# USB_PD.net
KiCad netlist of a schematic drawn in Altium Designer
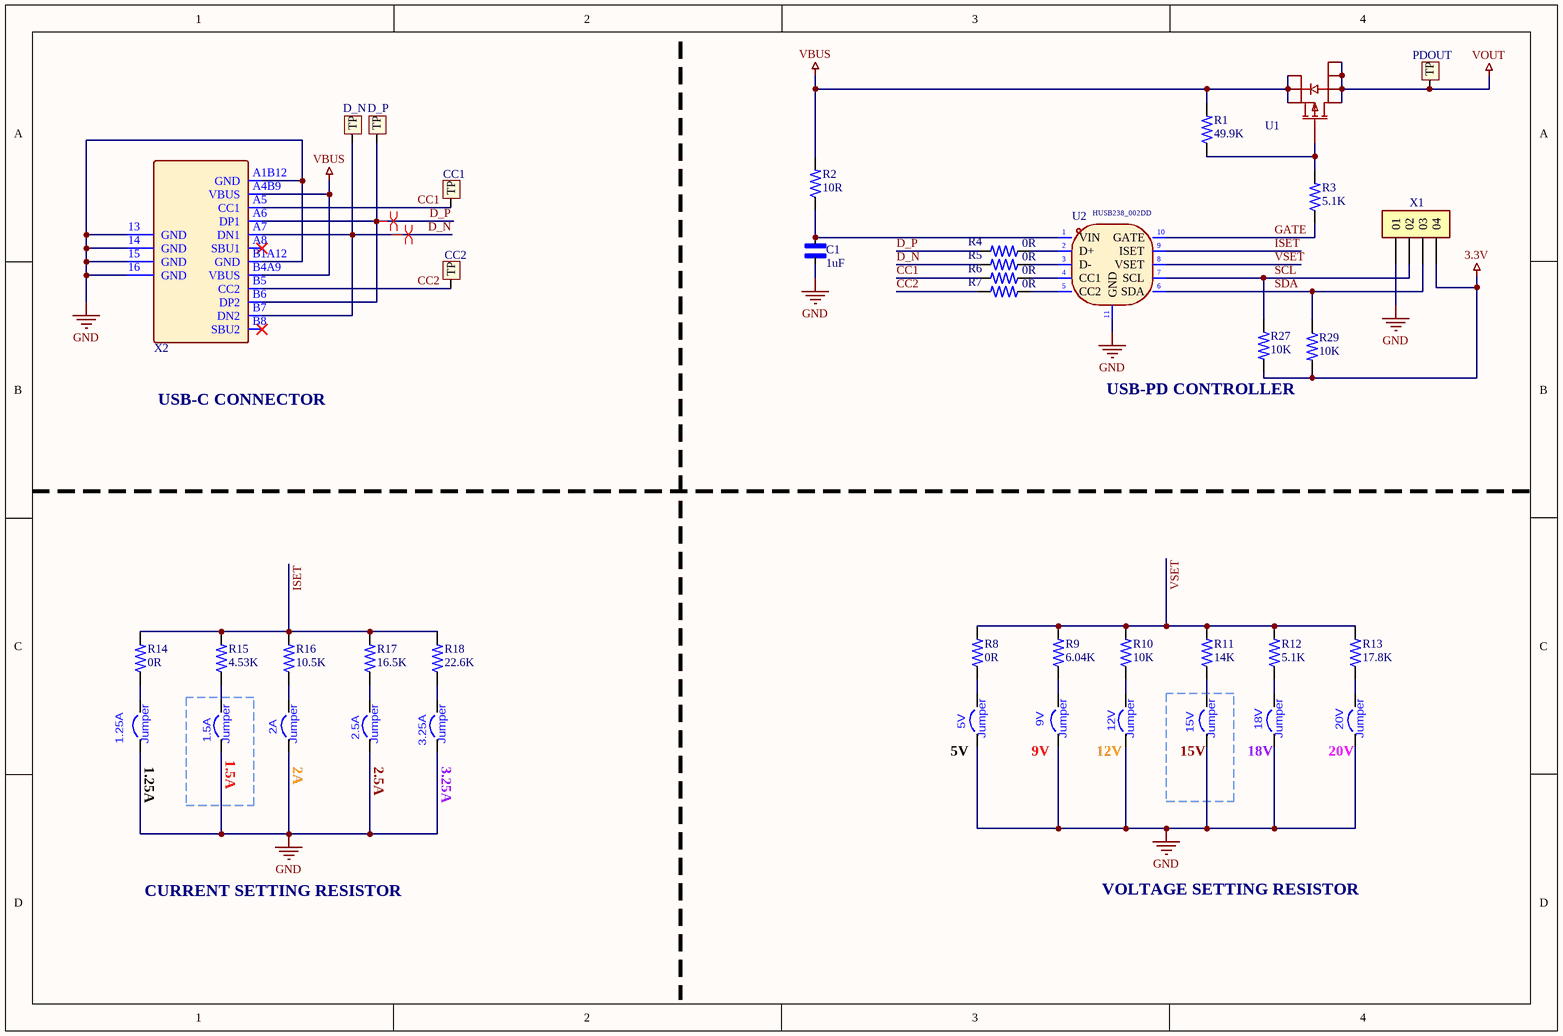
[diagram p0: USB_PD.SchDoc]

(export (version "E")
  (design (tool "Eeschema 10.0.6"))
  (components
    (comp (ref "1.5A")
      (value "Jumper")
      (footprint "PAD-JUMPER-2-NC_BY_PASTE_YES_SILK")
      (description "SMD JUMPER")
      (libsource (lib "USB_PD_DVD") (part "JUMPER SOLDER BRIDGE"))
    )
    (comp (ref "1.25A")
      (value "Jumper")
      (footprint "PAD-JUMPER-2-NC_BY_PASTE_YES_SILK")
      (description "SMD JUMPER")
      (libsource (lib "USB_PD_DVD") (part "JUMPER SOLDER BRIDGE"))
    )
    (comp (ref "2.5A")
      (value "Jumper")
      (footprint "PAD-JUMPER-2-NC_BY_PASTE_YES_SILK")
      (description "SMD JUMPER")
      (libsource (lib "USB_PD_DVD") (part "JUMPER SOLDER BRIDGE"))
    )
    (comp (ref "2A")
      (value "Jumper")
      (footprint "PAD-JUMPER-2-NC_BY_PASTE_YES_SILK")
      (description "SMD JUMPER")
      (libsource (lib "USB_PD_DVD") (part "JUMPER SOLDER BRIDGE"))
    )
    (comp (ref "3.25A")
      (value "Jumper")
      (footprint "PAD-JUMPER-2-NC_BY_PASTE_YES_SILK")
      (description "SMD JUMPER")
      (libsource (lib "USB_PD_DVD") (part "JUMPER SOLDER BRIDGE"))
    )
    (comp (ref "5V")
      (value "Jumper")
      (footprint "PAD-JUMPER-2-NC_BY_PASTE_YES_SILK")
      (description "SMD JUMPER")
      (libsource (lib "USB_PD_DVD") (part "JUMPER SOLDER BRIDGE"))
    )
    (comp (ref "9V")
      (value "Jumper")
      (footprint "PAD-JUMPER-2-NC_BY_PASTE_YES_SILK")
      (description "SMD JUMPER")
      (libsource (lib "USB_PD_DVD") (part "JUMPER SOLDER BRIDGE"))
    )
    (comp (ref "12V")
      (value "Jumper")
      (footprint "PAD-JUMPER-2-NC_BY_PASTE_YES_SILK")
      (description "SMD JUMPER")
      (libsource (lib "USB_PD_DVD") (part "JUMPER SOLDER BRIDGE"))
    )
    (comp (ref "15V")
      (value "Jumper")
      (footprint "PAD-JUMPER-2-NC_BY_PASTE_YES_SILK")
      (description "SMD JUMPER")
      (libsource (lib "USB_PD_DVD") (part "JUMPER SOLDER BRIDGE"))
    )
    (comp (ref "18V")
      (value "Jumper")
      (footprint "PAD-JUMPER-2-NC_BY_PASTE_YES_SILK")
      (description "SMD JUMPER")
      (libsource (lib "USB_PD_DVD") (part "JUMPER SOLDER BRIDGE"))
    )
    (comp (ref "20V")
      (value "Jumper")
      (footprint "PAD-JUMPER-2-NC_BY_PASTE_YES_SILK")
      (description "SMD JUMPER")
      (libsource (lib "USB_PD_DVD") (part "JUMPER SOLDER BRIDGE"))
    )
    (comp (ref "C1")
      (value "1uF")
      (footprint "CAP 0402")
      (fields
        (field (name "VOLTAGE") "50V")
        (field (name "TOLERANCE") "±10%")
        (field (name "Comment") "SMD capacitor")
      )
      (libsource (lib "USB_PD_DVD") (part "CAP_SMD_CERAMIC"))
    )
    (comp (ref "CC1")
      (value "TEST POINT")
      (footprint "TESTPOINT")
      (libsource (lib "USB_PD_DVD") (part "TEST POINT"))
    )
    (comp (ref "CC2")
      (value "TEST POINT")
      (footprint "TESTPOINT")
      (libsource (lib "USB_PD_DVD") (part "TEST POINT"))
    )
    (comp (ref "D_N")
      (value "TEST POINT")
      (footprint "TESTPOINT")
      (libsource (lib "USB_PD_DVD") (part "TEST POINT"))
    )
    (comp (ref "D_P")
      (value "TEST POINT")
      (footprint "TESTPOINT")
      (libsource (lib "USB_PD_DVD") (part "TEST POINT"))
    )
    (comp (ref "PDOUT")
      (value "TEST POINT")
      (footprint "TESTPOINT")
      (libsource (lib "USB_PD_DVD") (part "TEST POINT"))
    )
    (comp (ref "R1")
      (value "49.9K")
      (footprint "RES_1206")
      (fields (field (name "TOLERANCE") "±5%") (field (name "Comment") "SMD resistor"))
      (libsource (lib "USB_PD_DVD") (part "RES_SMD_CERAMIC"))
    )
    (comp (ref "R2")
      (value "10R")
      (footprint "RES_0603")
      (fields (field (name "TOLERANCE") "±5%") (field (name "Comment") "SMD resistor"))
      (libsource (lib "USB_PD_DVD") (part "RES_SMD_CERAMIC"))
    )
    (comp (ref "R3")
      (value "5.1K")
      (footprint "RES_1206")
      (fields (field (name "TOLERANCE") "±5%") (field (name "Comment") "SMD resistor"))
      (libsource (lib "USB_PD_DVD") (part "RES_SMD_CERAMIC"))
    )
    (comp (ref "R4")
      (value "0R")
      (footprint "RES 0402")
      (fields (field (name "TOLERANCE") "±5%") (field (name "Comment") "SMD resistor"))
      (libsource (lib "USB_PD_DVD") (part "RES_SMD_CERAMIC"))
    )
    (comp (ref "R5")
      (value "0R")
      (footprint "RES 0402")
      (fields (field (name "TOLERANCE") "±5%") (field (name "Comment") "SMD resistor"))
      (libsource (lib "USB_PD_DVD") (part "RES_SMD_CERAMIC"))
    )
    (comp (ref "R6")
      (value "0R")
      (footprint "RES 0402")
      (fields (field (name "TOLERANCE") "±5%") (field (name "Comment") "SMD resistor"))
      (libsource (lib "USB_PD_DVD") (part "RES_SMD_CERAMIC"))
    )
    (comp (ref "R7")
      (value "0R")
      (footprint "RES 0402")
      (fields (field (name "TOLERANCE") "±5%") (field (name "Comment") "SMD resistor"))
      (libsource (lib "USB_PD_DVD") (part "RES_SMD_CERAMIC"))
    )
    (comp (ref "R8")
      (value "0R")
      (footprint "RES 0402")
      (fields (field (name "TOLERANCE") "±5%") (field (name "Comment") "SMD resistor"))
      (libsource (lib "USB_PD_DVD") (part "RES_SMD_CERAMIC"))
    )
    (comp (ref "R9")
      (value "6.04K")
      (footprint "RES 0402")
      (fields (field (name "TOLERANCE") "±5%") (field (name "Comment") "SMD resistor"))
      (libsource (lib "USB_PD_DVD") (part "RES_SMD_CERAMIC"))
    )
    (comp (ref "R10")
      (value "10K")
      (footprint "RES 0402")
      (fields (field (name "TOLERANCE") "±5%") (field (name "Comment") "SMD resistor"))
      (libsource (lib "USB_PD_DVD") (part "RES_SMD_CERAMIC"))
    )
    (comp (ref "R11")
      (value "14K")
      (footprint "RES 0402")
      (fields (field (name "TOLERANCE") "±5%") (field (name "Comment") "SMD resistor"))
      (libsource (lib "USB_PD_DVD") (part "RES_SMD_CERAMIC"))
    )
    (comp (ref "R12")
      (value "5.1K")
      (footprint "RES 0402")
      (fields (field (name "TOLERANCE") "±5%") (field (name "Comment") "SMD resistor"))
      (libsource (lib "USB_PD_DVD") (part "RES_SMD_CERAMIC"))
    )
    (comp (ref "R13")
      (value "17.8K")
      (footprint "RES 0402")
      (fields (field (name "TOLERANCE") "±5%") (field (name "Comment") "SMD resistor"))
      (libsource (lib "USB_PD_DVD") (part "RES_SMD_CERAMIC"))
    )
    (comp (ref "R14")
      (value "0R")
      (footprint "RES 0402")
      (fields (field (name "TOLERANCE") "±5%") (field (name "Comment") "SMD resistor"))
      (libsource (lib "USB_PD_DVD") (part "RES_SMD_CERAMIC"))
    )
    (comp (ref "R15")
      (value "4.53K")
      (footprint "RES 0402")
      (fields (field (name "TOLERANCE") "±5%") (field (name "Comment") "SMD resistor"))
      (libsource (lib "USB_PD_DVD") (part "RES_SMD_CERAMIC"))
    )
    (comp (ref "R16")
      (value "10.5K")
      (footprint "RES 0402")
      (fields (field (name "TOLERANCE") "±5%") (field (name "Comment") "SMD resistor"))
      (libsource (lib "USB_PD_DVD") (part "RES_SMD_CERAMIC"))
    )
    (comp (ref "R17")
      (value "16.5K")
      (footprint "RES 0402")
      (fields (field (name "TOLERANCE") "±5%") (field (name "Comment") "SMD resistor"))
      (libsource (lib "USB_PD_DVD") (part "RES_SMD_CERAMIC"))
    )
    (comp (ref "R18")
      (value "22.6K")
      (footprint "RES 0402")
      (fields (field (name "TOLERANCE") "±5%") (field (name "Comment") "SMD resistor"))
      (libsource (lib "USB_PD_DVD") (part "RES_SMD_CERAMIC"))
    )
    (comp (ref "R27")
      (value "10K")
      (footprint "RES 0402")
      (fields (field (name "TOLERANCE") "±5%") (field (name "Comment") "SMD resistor NC"))
      (libsource (lib "USB_PD_DVD") (part "RES_SMD_CERAMIC"))
    )
    (comp (ref "R29")
      (value "10K")
      (footprint "RES 0402")
      (fields (field (name "TOLERANCE") "±5%") (field (name "Comment") "SMD resistor NC"))
      (libsource (lib "USB_PD_DVD") (part "RES_SMD_CERAMIC"))
    )
    (comp (ref "U1")
      (value "P-Channel  MOSFET")
      (footprint "PRPAK-8_L3.0-W3.0-P0.65-BL-EP")
      (description "30V 24A 9.2mΩ@10V 1.8V@250uA 1 P-Channel DFN-8(3x3) MOSFETs ROHS")
      (fields
        (field (name "MANIFACTURING PART NUMBER") "AONR21307")
        (field (name "JLCPCB PART #") "C3277813")
      )
      (libsource (lib "USB_PD_DVD") (part "AONR21307"))
    )
    (comp (ref "U2")
      (value "HUSB238_002DD")
      (footprint "DFN-10")
      (description "DFN-10L(3x3) USB Converters ROHS")
      (fields (field (name "JLCPCB PART #") "C7471904") (field (name "Comment") "USB-PD-IC"))
      (libsource (lib "USB_PD_DVD") (part "USB_PD_HUSB238"))
    )
    (comp (ref "X1")
      (value "Header X 5")
      (footprint "SAMTEC_TS-104-T-A")
      (description "4 pin header pitch 2.54mm")
      (fields (field (name "MANIFACTURING PART NUMBER") "C91552"))
      (libsource (lib "USB_PD_DVD") (part "4 Pin Header"))
    )
    (comp (ref "X2")
      (value "USB-C connector")
      (footprint "USB-C-SMD_TYPEC-304J-BCP16")
      (description "5A USB 3.1 1 Surface Mount, Right Angle 16P Female -40℃~+85℃ Type-C SMD USB Connectors ROHS")
      (fields
        (field (name "MANIFACTURING PART NUMBER") "TYPEC-304J-BCP16")
        (field (name "JLCPCB PART #") "C2835315")
      )
      (libsource (lib "USB_PD_DVD") (part "TYPEC-304J-BCP16"))
    )
  )
  (nets
    (net (code "1") (name "/CC1") (class "Default")
      (node (ref "CC1") (pin "1") (pinfunction "TP_1") (pintype "passive"))
      (node (ref "R6") (pin "2") (pinfunction "2_2") (pintype "passive"))
      (node (ref "X2") (pin "A5") (pinfunction "CC1_A5") (pintype "passive"))
    )
    (net (code "2") (name "/CC2") (class "Default")
      (node (ref "CC2") (pin "1") (pinfunction "TP_1") (pintype "passive"))
      (node (ref "R7") (pin "2") (pinfunction "2_2") (pintype "passive"))
      (node (ref "X2") (pin "B5") (pinfunction "CC2_B5") (pintype "passive"))
    )
    (net (code "3") (name "/D_N") (class "Default")
      (node (ref "D_N") (pin "1") (pinfunction "TP_1") (pintype "passive"))
      (node (ref "R5") (pin "2") (pinfunction "2_2") (pintype "passive"))
      (node (ref "X2") (pin "A7") (pinfunction "DN1_A7") (pintype "passive"))
      (node (ref "X2") (pin "B7") (pinfunction "DN2_B7") (pintype "passive"))
    )
    (net (code "4") (name "/D_P") (class "Default")
      (node (ref "D_P") (pin "1") (pinfunction "TP_1") (pintype "passive"))
      (node (ref "R4") (pin "2") (pinfunction "2_2") (pintype "passive"))
      (node (ref "X2") (pin "A6") (pinfunction "DP1_A6") (pintype "passive"))
      (node (ref "X2") (pin "B6") (pinfunction "DP2_B6") (pintype "passive"))
    )
    (net (code "5") (name "/GATE") (class "Default")
      (node (ref "R3") (pin "1") (pinfunction "1_1") (pintype "passive"))
      (node (ref "U2") (pin "10") (pinfunction "GATE_10") (pintype "passive"))
    )
    (net (code "6") (name "/ISET") (class "Default")
      (node (ref "R14") (pin "2") (pinfunction "2_2") (pintype "passive"))
      (node (ref "R15") (pin "2") (pinfunction "2_2") (pintype "passive"))
      (node (ref "R16") (pin "2") (pinfunction "2_2") (pintype "passive"))
      (node (ref "R17") (pin "2") (pinfunction "2_2") (pintype "passive"))
      (node (ref "R18") (pin "2") (pinfunction "2_2") (pintype "passive"))
      (node (ref "U2") (pin "9") (pinfunction "ISET_9") (pintype "passive"))
    )
    (net (code "7") (name "/SCL") (class "Default")
      (node (ref "R27") (pin "1") (pinfunction "1_1") (pintype "passive"))
      (node (ref "U2") (pin "7") (pinfunction "SCL_7") (pintype "passive"))
      (node (ref "X1") (pin "02") (pinfunction "02_02") (pintype "passive"))
    )
    (net (code "8") (name "/SDA") (class "Default")
      (node (ref "R29") (pin "1") (pinfunction "1_1") (pintype "passive"))
      (node (ref "U2") (pin "6") (pinfunction "SDA_6") (pintype "passive"))
      (node (ref "X1") (pin "03") (pinfunction "03_03") (pintype "passive"))
    )
    (net (code "9") (name "/VSET") (class "Default")
      (node (ref "R10") (pin "2") (pinfunction "2_2") (pintype "passive"))
      (node (ref "R11") (pin "2") (pinfunction "2_2") (pintype "passive"))
      (node (ref "R12") (pin "2") (pinfunction "2_2") (pintype "passive"))
      (node (ref "R13") (pin "2") (pinfunction "2_2") (pintype "passive"))
      (node (ref "R8") (pin "2") (pinfunction "2_2") (pintype "passive"))
      (node (ref "R9") (pin "2") (pinfunction "2_2") (pintype "passive"))
      (node (ref "U2") (pin "8") (pinfunction "VSET_8") (pintype "passive"))
    )
    (net (code "10") (name "3.3V") (class "Default")
      (node (ref "R27") (pin "2") (pinfunction "2_2") (pintype "passive"))
      (node (ref "R29") (pin "2") (pinfunction "2_2") (pintype "passive"))
      (node (ref "X1") (pin "04") (pinfunction "04_04") (pintype "passive"))
    )
    (net (code "11") (name "GND") (class "Default")
      (node (ref "1.25A") (pin "1") (pinfunction "1_1") (pintype "passive"))
      (node (ref "1.5A") (pin "1") (pinfunction "1_1") (pintype "passive"))
      (node (ref "12V") (pin "1") (pinfunction "1_1") (pintype "passive"))
      (node (ref "15V") (pin "1") (pinfunction "1_1") (pintype "passive"))
      (node (ref "18V") (pin "1") (pinfunction "1_1") (pintype "passive"))
      (node (ref "2.5A") (pin "1") (pinfunction "1_1") (pintype "passive"))
      (node (ref "20V") (pin "1") (pinfunction "1_1") (pintype "passive"))
      (node (ref "2A") (pin "1") (pinfunction "1_1") (pintype "passive"))
      (node (ref "3.25A") (pin "1") (pinfunction "1_1") (pintype "passive"))
      (node (ref "5V") (pin "1") (pinfunction "1_1") (pintype "passive"))
      (node (ref "9V") (pin "1") (pinfunction "1_1") (pintype "passive"))
      (node (ref "C1") (pin "2") (pinfunction "2_2") (pintype "passive"))
      (node (ref "U2") (pin "11") (pinfunction "GND_11") (pintype "passive"))
      (node (ref "X1") (pin "01") (pinfunction "01_01") (pintype "passive"))
      (node (ref "X2") (pin "13") (pinfunction "GND_13") (pintype "passive"))
      (node (ref "X2") (pin "14") (pinfunction "GND_14") (pintype "passive"))
      (node (ref "X2") (pin "15") (pinfunction "GND_15") (pintype "passive"))
      (node (ref "X2") (pin "16") (pinfunction "GND_16") (pintype "passive"))
      (node (ref "X2") (pin "A1B12") (pinfunction "GND_A1B12") (pintype "passive"))
      (node (ref "X2") (pin "B1A12") (pinfunction "GND_B1A12") (pintype "passive"))
    )
    (net (code "12") (name "Net-(1.5A-Pad2)") (class "Default")
      (node (ref "1.5A") (pin "2") (pinfunction "2_2") (pintype "passive"))
      (node (ref "R15") (pin "1") (pinfunction "1_1") (pintype "passive"))
    )
    (net (code "13") (name "Net-(1.25A-Pad2)") (class "Default")
      (node (ref "1.25A") (pin "2") (pinfunction "2_2") (pintype "passive"))
      (node (ref "R14") (pin "1") (pinfunction "1_1") (pintype "passive"))
    )
    (net (code "14") (name "Net-(2.5A-Pad2)") (class "Default")
      (node (ref "2.5A") (pin "2") (pinfunction "2_2") (pintype "passive"))
      (node (ref "R17") (pin "1") (pinfunction "1_1") (pintype "passive"))
    )
    (net (code "15") (name "Net-(2A-Pad2)") (class "Default")
      (node (ref "2A") (pin "2") (pinfunction "2_2") (pintype "passive"))
      (node (ref "R16") (pin "1") (pinfunction "1_1") (pintype "passive"))
    )
    (net (code "16") (name "Net-(3.25A-Pad2)") (class "Default")
      (node (ref "3.25A") (pin "2") (pinfunction "2_2") (pintype "passive"))
      (node (ref "R18") (pin "1") (pinfunction "1_1") (pintype "passive"))
    )
    (net (code "17") (name "Net-(5V-Pad2)") (class "Default")
      (node (ref "5V") (pin "2") (pinfunction "2_2") (pintype "passive"))
      (node (ref "R8") (pin "1") (pinfunction "1_1") (pintype "passive"))
    )
    (net (code "18") (name "Net-(9V-Pad2)") (class "Default")
      (node (ref "9V") (pin "2") (pinfunction "2_2") (pintype "passive"))
      (node (ref "R9") (pin "1") (pinfunction "1_1") (pintype "passive"))
    )
    (net (code "19") (name "Net-(12V-Pad2)") (class "Default")
      (node (ref "12V") (pin "2") (pinfunction "2_2") (pintype "passive"))
      (node (ref "R10") (pin "1") (pinfunction "1_1") (pintype "passive"))
    )
    (net (code "20") (name "Net-(15V-Pad2)") (class "Default")
      (node (ref "15V") (pin "2") (pinfunction "2_2") (pintype "passive"))
      (node (ref "R11") (pin "1") (pinfunction "1_1") (pintype "passive"))
    )
    (net (code "21") (name "Net-(18V-Pad2)") (class "Default")
      (node (ref "18V") (pin "2") (pinfunction "2_2") (pintype "passive"))
      (node (ref "R12") (pin "1") (pinfunction "1_1") (pintype "passive"))
    )
    (net (code "22") (name "Net-(20V-Pad2)") (class "Default")
      (node (ref "20V") (pin "2") (pinfunction "2_2") (pintype "passive"))
      (node (ref "R13") (pin "1") (pinfunction "1_1") (pintype "passive"))
    )
    (net (code "23") (name "Net-(U1-G)") (class "Default")
      (node (ref "R1") (pin "1") (pinfunction "1_1") (pintype "passive"))
      (node (ref "R3") (pin "2") (pinfunction "2_2") (pintype "passive"))
      (node (ref "U1") (pin "4") (pinfunction "G_4") (pintype "passive"))
    )
    (net (code "24") (name "Net-(U2-CC1)") (class "Default")
      (node (ref "R6") (pin "1") (pinfunction "1_1") (pintype "passive"))
      (node (ref "U2") (pin "4") (pinfunction "CC1_4") (pintype "passive"))
    )
    (net (code "25") (name "Net-(U2-CC2)") (class "Default")
      (node (ref "R7") (pin "1") (pinfunction "1_1") (pintype "passive"))
      (node (ref "U2") (pin "5") (pinfunction "CC2_5") (pintype "passive"))
    )
    (net (code "26") (name "Net-(U2-D+)") (class "Default")
      (node (ref "R4") (pin "1") (pinfunction "1_1") (pintype "passive"))
      (node (ref "U2") (pin "2") (pinfunction "D+_2") (pintype "passive"))
    )
    (net (code "27") (name "Net-(U2-D-)") (class "Default")
      (node (ref "R5") (pin "1") (pinfunction "1_1") (pintype "passive"))
      (node (ref "U2") (pin "3") (pinfunction "D-_3") (pintype "passive"))
    )
    (net (code "28") (name "Net-(U2-VIN)") (class "Default")
      (node (ref "C1") (pin "1") (pinfunction "1_1") (pintype "passive"))
      (node (ref "R2") (pin "1") (pinfunction "1_1") (pintype "passive"))
      (node (ref "U2") (pin "1") (pinfunction "VIN_1") (pintype "passive"))
    )
    (net (code "29") (name "VBUS") (class "Default")
      (node (ref "R1") (pin "2") (pinfunction "2_2") (pintype "passive"))
      (node (ref "R2") (pin "2") (pinfunction "2_2") (pintype "passive"))
      (node (ref "U1") (pin "1") (pinfunction "S_1") (pintype "passive"))
      (node (ref "U1") (pin "2") (pinfunction "S_2") (pintype "passive"))
      (node (ref "U1") (pin "3") (pinfunction "S_3") (pintype "passive"))
      (node (ref "X2") (pin "A4B9") (pinfunction "VBUS_A4B9") (pintype "passive"))
      (node (ref "X2") (pin "B4A9") (pinfunction "VBUS_B4A9") (pintype "passive"))
    )
    (net (code "30") (name "VOUT") (class "Default")
      (node (ref "PDOUT") (pin "1") (pinfunction "TP_1") (pintype "passive"))
      (node (ref "U1") (pin "5") (pinfunction "D_5") (pintype "passive"))
      (node (ref "U1") (pin "6") (pinfunction "D_6") (pintype "passive"))
      (node (ref "U1") (pin "7") (pinfunction "D_7") (pintype "passive"))
      (node (ref "U1") (pin "8") (pinfunction "D_8") (pintype "passive"))
    )
    (net (code "31") (name "unconnected-(X2-SBU1-PadA8)") (class "Default")
      (node (ref "X2") (pin "A8") (pinfunction "SBU1_A8") (pintype "passive+no_connect"))
    )
    (net (code "32") (name "unconnected-(X2-SBU2-PadB8)") (class "Default")
      (node (ref "X2") (pin "B8") (pinfunction "SBU2_B8") (pintype "passive+no_connect"))
    )
  )
)
